# GPIO_Direct.net
KiCad netlist of a schematic drawn in Altium Designer
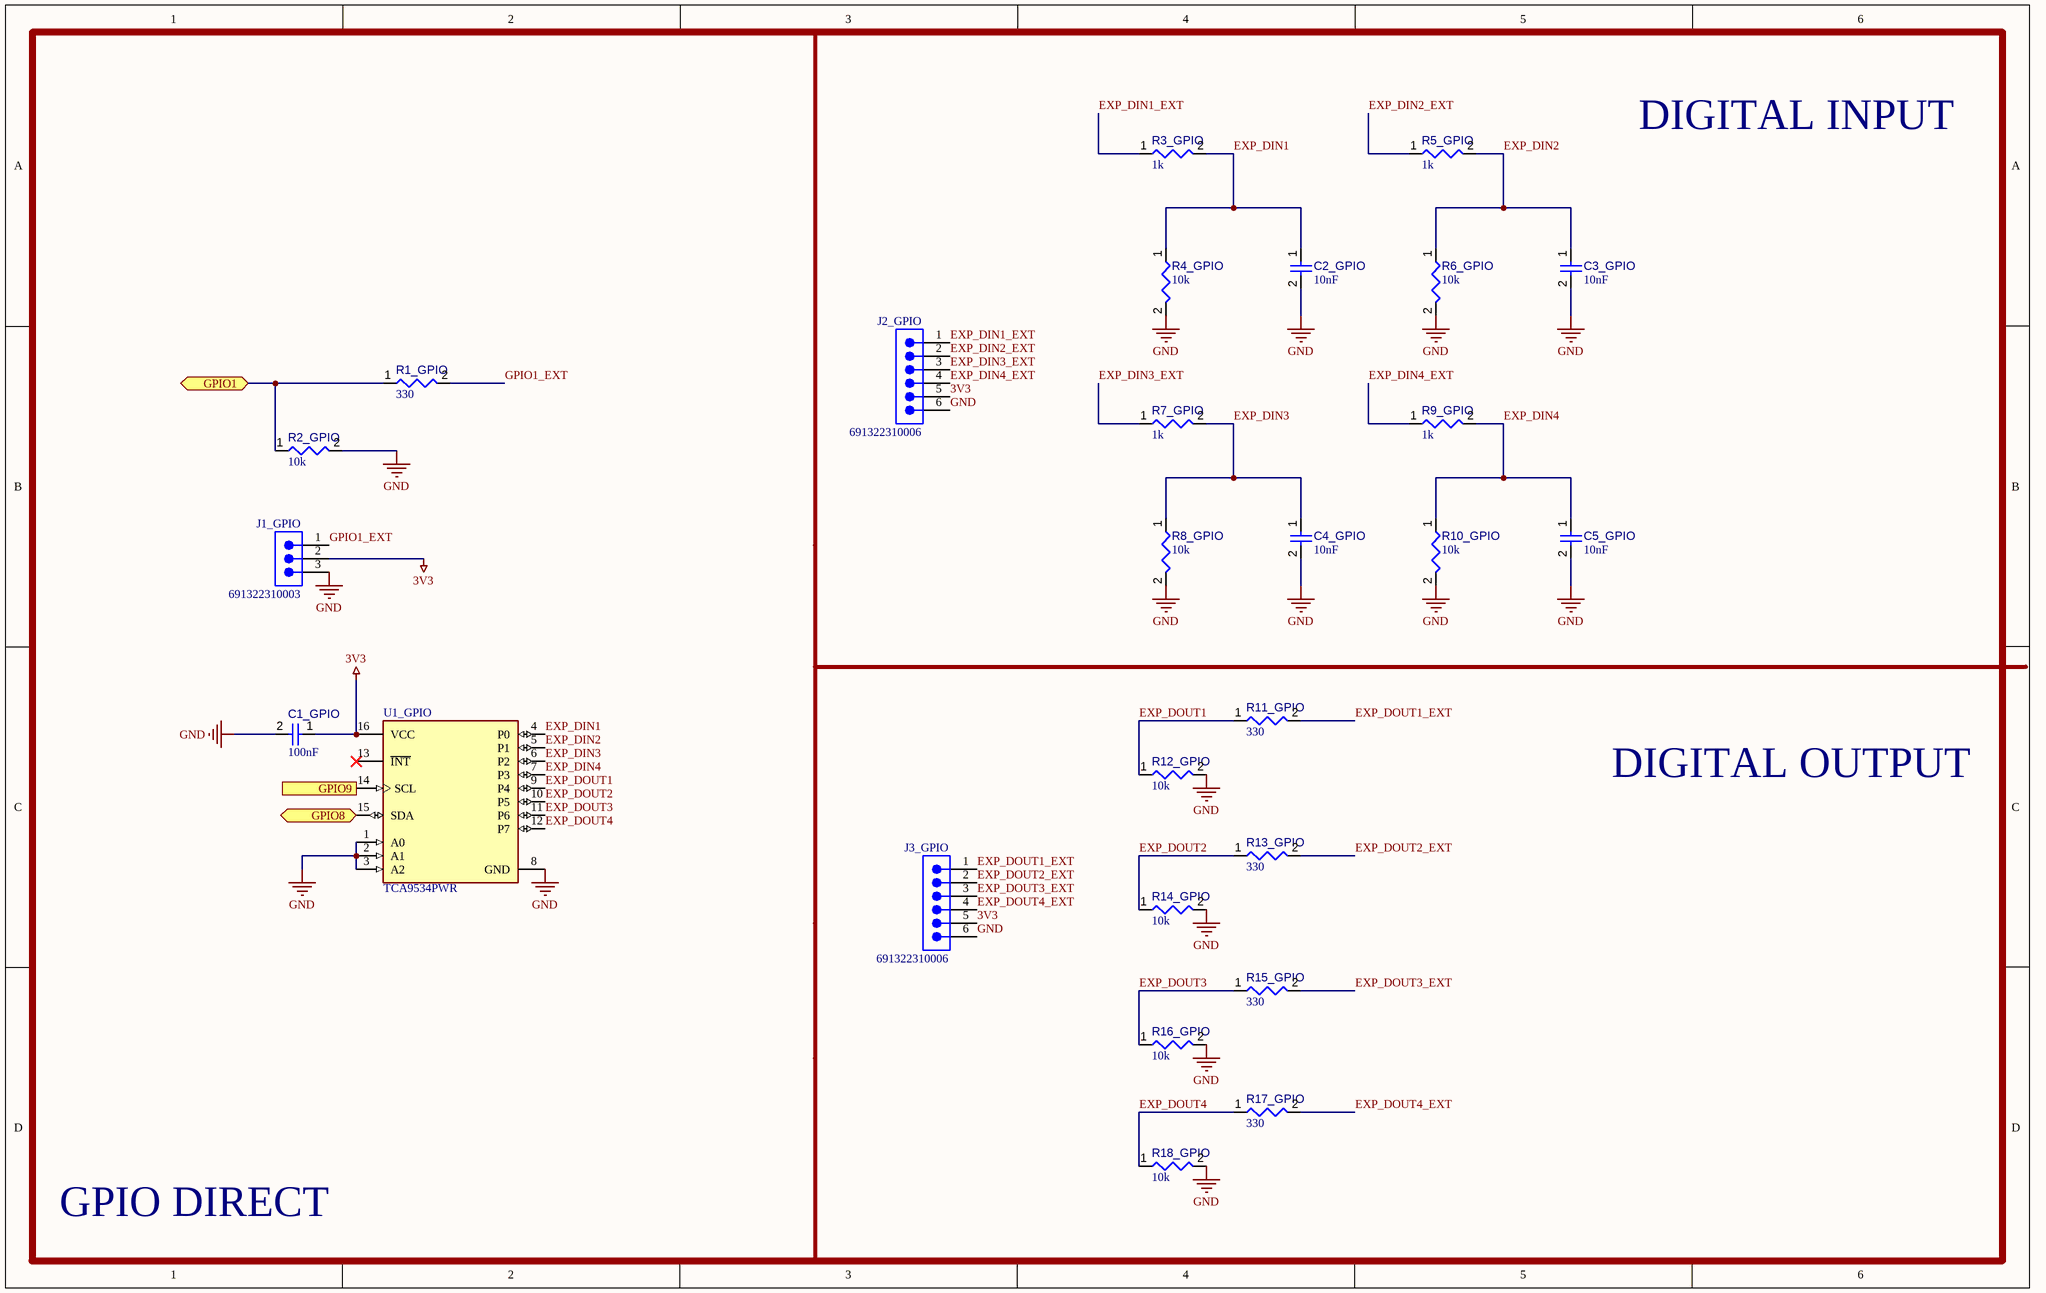
[diagram p0: GPIO Direct.SchDoc]

(export (version "E")
  (design (tool "Eeschema 10.0.6"))
  (components
    (comp (ref "C1_GPIO")
      (value "100nF")
      (footprint "CAPC1608X90X40NL10T20")
      (description "Chip Capacitor, 100 nF, +/- 10%, 50 V, 0603 (1608 Metric)")
      (fields (field (name "TOLERANCE") "10%") (field (name "Comment") "Capacitor 100 nF +/-10% 50 V 0603"))
      (libsource (lib "Faiz Agunda") (part "CAP-NP-2"))
    )
    (comp (ref "C2_GPIO")
      (value "10nF")
      (footprint "CAPC0402(1005)60_L")
      (description "Chip Capacitor, 10nF +/-20%, 50V, 0402, Thickness 0.6 mm")
      (fields (field (name "TOLERANCE") "5%") (field (name "Comment") "Capacitor 10nF +/-20% 50V 0402"))
      (libsource (lib "Faiz Agunda") (part "CAP-NP-2"))
    )
    (comp (ref "C3_GPIO")
      (value "10nF")
      (footprint "CAPC0402(1005)60_L")
      (description "Chip Capacitor, 10nF +/-20%, 50V, 0402, Thickness 0.6 mm")
      (fields (field (name "TOLERANCE") "5%") (field (name "Comment") "Capacitor 10nF +/-20% 50V 0402"))
      (libsource (lib "Faiz Agunda") (part "CAP-NP-2"))
    )
    (comp (ref "C4_GPIO")
      (value "10nF")
      (footprint "CAPC0402(1005)60_L")
      (description "Chip Capacitor, 10nF +/-20%, 50V, 0402, Thickness 0.6 mm")
      (fields (field (name "TOLERANCE") "5%") (field (name "Comment") "Capacitor 10nF +/-20% 50V 0402"))
      (libsource (lib "Faiz Agunda") (part "CAP-NP-2"))
    )
    (comp (ref "C5_GPIO")
      (value "10nF")
      (footprint "CAPC0402(1005)60_L")
      (description "Chip Capacitor, 10nF +/-20%, 50V, 0402, Thickness 0.6 mm")
      (fields (field (name "TOLERANCE") "5%") (field (name "Comment") "Capacitor 10nF +/-20% 50V 0402"))
      (libsource (lib "Faiz Agunda") (part "CAP-NP-2"))
    )
    (comp (ref "J1_GPIO")
      (value "691322310003")
      (footprint "691322310003")
      (description "Wurth Elektronik 3.81mmpitch3pPlug-in terminal blocks socket head, 322series, 300.0 v, welding")
      (fields (field (name "VOLTAGE") "300V"))
      (libsource (lib "Faiz Agunda") (part "TBL - 1R - 03P - Male"))
    )
    (comp (ref "J2_GPIO")
      (value "691322310006")
      (footprint "691322310006")
      (description "Wurth Elektronik 3.81mmpitch6pPlug-in terminal blocks socket head, 322series, 300.0 v, welding")
      (fields (field (name "VOLTAGE") "300V"))
      (libsource (lib "Faiz Agunda") (part "TBL - 1R - 06P - Male"))
    )
    (comp (ref "J3_GPIO")
      (value "691322310006")
      (footprint "691322310006")
      (description "Wurth Elektronik 3.81mmpitch6pPlug-in terminal blocks socket head, 322series, 300.0 v, welding")
      (fields (field (name "VOLTAGE") "300V"))
      (libsource (lib "Faiz Agunda") (part "TBL - 1R - 06P - Male"))
    )
    (comp (ref "R1_GPIO")
      (value "330")
      (footprint "RESC0402(1005)_L")
      (description "Chip Resistor, 330 Ohms, +/-5 %, 63 mW, -55 to 155 degC, 0402")
      (fields (field (name "POWER") "63mW") (field (name "TOLERANCE") "5%"))
      (libsource (lib "Faiz Agunda") (part "RES-2"))
    )
    (comp (ref "R2_GPIO")
      (value "10k")
      (footprint "RESC0402(1005)_L")
      (description "Chip Resistor, 10 kOhms, +/-1 %, 63 mW, -55 to 125 degC, 0402")
      (fields (field (name "POWER") "63mW") (field (name "TOLERANCE") "1%"))
      (libsource (lib "Faiz Agunda") (part "RES-2"))
    )
    (comp (ref "R3_GPIO")
      (value "1k")
      (footprint "RESC1608X55X25ML10T15")
      (description "Chip Resistor, 1 KOhm, +/-1%, 0.1 W, -55 to 155 degC, 0603 (1608 Metric)")
      (fields (field (name "POWER") "100mW") (field (name "TOLERANCE") "1%"))
      (libsource (lib "Faiz Agunda") (part "RES-2"))
    )
    (comp (ref "R4_GPIO")
      (value "10k")
      (footprint "RESC1005X40X25ML05T05")
      (description "Chip Resistor, 10 KOhm, +/- 1%, 63 mW, -55 to 155 degC, 0402 (1005 Metric)")
      (fields (field (name "POWER") "63mW") (field (name "TOLERANCE") "1%"))
      (libsource (lib "Faiz Agunda") (part "RES-2"))
    )
    (comp (ref "R5_GPIO")
      (value "1k")
      (footprint "RESC1608X55X25ML10T15")
      (description "Chip Resistor, 1 KOhm, +/-1%, 0.1 W, -55 to 155 degC, 0603 (1608 Metric)")
      (fields (field (name "POWER") "100mW") (field (name "TOLERANCE") "1%"))
      (libsource (lib "Faiz Agunda") (part "RES-2"))
    )
    (comp (ref "R6_GPIO")
      (value "10k")
      (footprint "RESC1005X40X25ML05T05")
      (description "Chip Resistor, 10 KOhm, +/- 1%, 63 mW, -55 to 155 degC, 0402 (1005 Metric)")
      (fields (field (name "POWER") "63mW") (field (name "TOLERANCE") "1%"))
      (libsource (lib "Faiz Agunda") (part "RES-2"))
    )
    (comp (ref "R7_GPIO")
      (value "1k")
      (footprint "RESC1608X55X25ML10T15")
      (description "Chip Resistor, 1 KOhm, +/-1%, 0.1 W, -55 to 155 degC, 0603 (1608 Metric)")
      (fields (field (name "POWER") "100mW") (field (name "TOLERANCE") "1%"))
      (libsource (lib "Faiz Agunda") (part "RES-2"))
    )
    (comp (ref "R8_GPIO")
      (value "10k")
      (footprint "RESC1005X40X25ML05T05")
      (description "Chip Resistor, 10 KOhm, +/- 1%, 63 mW, -55 to 155 degC, 0402 (1005 Metric)")
      (fields (field (name "POWER") "63mW") (field (name "TOLERANCE") "1%"))
      (libsource (lib "Faiz Agunda") (part "RES-2"))
    )
    (comp (ref "R9_GPIO")
      (value "1k")
      (footprint "RESC1608X55X25ML10T15")
      (description "Chip Resistor, 1 KOhm, +/-1%, 0.1 W, -55 to 155 degC, 0603 (1608 Metric)")
      (fields (field (name "POWER") "100mW") (field (name "TOLERANCE") "1%"))
      (libsource (lib "Faiz Agunda") (part "RES-2"))
    )
    (comp (ref "R10_GPIO")
      (value "10k")
      (footprint "RESC1005X40X25ML05T05")
      (description "Chip Resistor, 10 KOhm, +/- 1%, 63 mW, -55 to 155 degC, 0402 (1005 Metric)")
      (fields (field (name "POWER") "63mW") (field (name "TOLERANCE") "1%"))
      (libsource (lib "Faiz Agunda") (part "RES-2"))
    )
    (comp (ref "R11_GPIO")
      (value "330")
      (footprint "RESC0402(1005)_L")
      (description "Chip Resistor, 330 Ohms, +/-5 %, 63 mW, -55 to 155 degC, 0402")
      (fields (field (name "POWER") "63mW") (field (name "TOLERANCE") "5%"))
      (libsource (lib "Faiz Agunda") (part "RES-2"))
    )
    (comp (ref "R12_GPIO")
      (value "10k")
      (footprint "RESC0402(1005)_L")
      (description "Chip Resistor, 10 kOhms, +/-1 %, 63 mW, -55 to 125 degC, 0402")
      (fields (field (name "POWER") "63mW") (field (name "TOLERANCE") "1%"))
      (libsource (lib "Faiz Agunda") (part "RES-2"))
    )
    (comp (ref "R13_GPIO")
      (value "330")
      (footprint "RESC0402(1005)_L")
      (description "Chip Resistor, 330 Ohms, +/-5 %, 63 mW, -55 to 155 degC, 0402")
      (fields (field (name "POWER") "63mW") (field (name "TOLERANCE") "5%"))
      (libsource (lib "Faiz Agunda") (part "RES-2"))
    )
    (comp (ref "R14_GPIO")
      (value "10k")
      (footprint "RESC0402(1005)_L")
      (description "Chip Resistor, 10 kOhms, +/-1 %, 63 mW, -55 to 125 degC, 0402")
      (fields (field (name "POWER") "63mW") (field (name "TOLERANCE") "1%"))
      (libsource (lib "Faiz Agunda") (part "RES-2"))
    )
    (comp (ref "R15_GPIO")
      (value "330")
      (footprint "RESC0402(1005)_L")
      (description "Chip Resistor, 330 Ohms, +/-5 %, 63 mW, -55 to 155 degC, 0402")
      (fields (field (name "POWER") "63mW") (field (name "TOLERANCE") "5%"))
      (libsource (lib "Faiz Agunda") (part "RES-2"))
    )
    (comp (ref "R16_GPIO")
      (value "10k")
      (footprint "RESC0402(1005)_L")
      (description "Chip Resistor, 10 kOhms, +/-1 %, 63 mW, -55 to 125 degC, 0402")
      (fields (field (name "POWER") "63mW") (field (name "TOLERANCE") "1%"))
      (libsource (lib "Faiz Agunda") (part "RES-2"))
    )
    (comp (ref "R17_GPIO")
      (value "330")
      (footprint "RESC0402(1005)_L")
      (description "Chip Resistor, 330 Ohms, +/-5 %, 63 mW, -55 to 155 degC, 0402")
      (fields (field (name "POWER") "63mW") (field (name "TOLERANCE") "5%"))
      (libsource (lib "Faiz Agunda") (part "RES-2"))
    )
    (comp (ref "R18_GPIO")
      (value "10k")
      (footprint "RESC0402(1005)_L")
      (description "Chip Resistor, 10 kOhms, +/-1 %, 63 mW, -55 to 125 degC, 0402")
      (fields (field (name "POWER") "63mW") (field (name "TOLERANCE") "1%"))
      (libsource (lib "Faiz Agunda") (part "RES-2"))
    )
    (comp (ref "U1_GPIO")
      (value "TCA9534PWR")
      (footprint "FP-PW0016A-IPC_B")
      (description "10mA 25mA I2C 8 1.65V 5.5V 400KHz yes TSSOP-16 SMD mount，glue mount 1.2mm(height)")
      (libsource (lib "Faiz Agunda") (part "04628dd91dbb09866b58f3fb2ae999f"))
    )
  )
  (nets
    (net (code "1") (name "/EXP_DIN1") (class "Default")
      (node (ref "C2_GPIO") (pin "1") (pinfunction "1_1") (pintype "passive"))
      (node (ref "R3_GPIO") (pin "2") (pinfunction "2_2") (pintype "passive"))
      (node (ref "R4_GPIO") (pin "1") (pinfunction "1_1") (pintype "passive"))
      (node (ref "U1_GPIO") (pin "4") (pinfunction "P0_4") (pintype "bidirectional"))
    )
    (net (code "2") (name "/EXP_DIN1_EXT") (class "Default")
      (node (ref "J2_GPIO") (pin "1") (pinfunction "1_1") (pintype "passive"))
      (node (ref "R3_GPIO") (pin "1") (pinfunction "1_1") (pintype "passive"))
    )
    (net (code "3") (name "/EXP_DIN2") (class "Default")
      (node (ref "C3_GPIO") (pin "1") (pinfunction "1_1") (pintype "passive"))
      (node (ref "R5_GPIO") (pin "2") (pinfunction "2_2") (pintype "passive"))
      (node (ref "R6_GPIO") (pin "1") (pinfunction "1_1") (pintype "passive"))
      (node (ref "U1_GPIO") (pin "5") (pinfunction "P1_5") (pintype "bidirectional"))
    )
    (net (code "4") (name "/EXP_DIN2_EXT") (class "Default")
      (node (ref "J2_GPIO") (pin "2") (pinfunction "2_2") (pintype "passive"))
      (node (ref "R5_GPIO") (pin "1") (pinfunction "1_1") (pintype "passive"))
    )
    (net (code "5") (name "/EXP_DIN3") (class "Default")
      (node (ref "C4_GPIO") (pin "1") (pinfunction "1_1") (pintype "passive"))
      (node (ref "R7_GPIO") (pin "2") (pinfunction "2_2") (pintype "passive"))
      (node (ref "R8_GPIO") (pin "1") (pinfunction "1_1") (pintype "passive"))
      (node (ref "U1_GPIO") (pin "6") (pinfunction "P2_6") (pintype "bidirectional"))
    )
    (net (code "6") (name "/EXP_DIN3_EXT") (class "Default")
      (node (ref "J2_GPIO") (pin "3") (pinfunction "3_3") (pintype "passive"))
      (node (ref "R7_GPIO") (pin "1") (pinfunction "1_1") (pintype "passive"))
    )
    (net (code "7") (name "/EXP_DIN4") (class "Default")
      (node (ref "C5_GPIO") (pin "1") (pinfunction "1_1") (pintype "passive"))
      (node (ref "R10_GPIO") (pin "1") (pinfunction "1_1") (pintype "passive"))
      (node (ref "R9_GPIO") (pin "2") (pinfunction "2_2") (pintype "passive"))
      (node (ref "U1_GPIO") (pin "7") (pinfunction "P3_7") (pintype "bidirectional"))
    )
    (net (code "8") (name "/EXP_DIN4_EXT") (class "Default")
      (node (ref "J2_GPIO") (pin "4") (pinfunction "4_4") (pintype "passive"))
      (node (ref "R9_GPIO") (pin "1") (pinfunction "1_1") (pintype "passive"))
    )
    (net (code "9") (name "/EXP_DOUT1") (class "Default")
      (node (ref "R11_GPIO") (pin "1") (pinfunction "1_1") (pintype "passive"))
      (node (ref "R12_GPIO") (pin "1") (pinfunction "1_1") (pintype "passive"))
      (node (ref "U1_GPIO") (pin "9") (pinfunction "P4_9") (pintype "bidirectional"))
    )
    (net (code "10") (name "/EXP_DOUT1_EXT") (class "Default")
      (node (ref "J3_GPIO") (pin "1") (pinfunction "1_1") (pintype "passive"))
      (node (ref "R11_GPIO") (pin "2") (pinfunction "2_2") (pintype "passive"))
    )
    (net (code "11") (name "/EXP_DOUT2") (class "Default")
      (node (ref "R13_GPIO") (pin "1") (pinfunction "1_1") (pintype "passive"))
      (node (ref "R14_GPIO") (pin "1") (pinfunction "1_1") (pintype "passive"))
      (node (ref "U1_GPIO") (pin "10") (pinfunction "P5_10") (pintype "bidirectional"))
    )
    (net (code "12") (name "/EXP_DOUT2_EXT") (class "Default")
      (node (ref "J3_GPIO") (pin "2") (pinfunction "2_2") (pintype "passive"))
      (node (ref "R13_GPIO") (pin "2") (pinfunction "2_2") (pintype "passive"))
    )
    (net (code "13") (name "/EXP_DOUT3") (class "Default")
      (node (ref "R15_GPIO") (pin "1") (pinfunction "1_1") (pintype "passive"))
      (node (ref "R16_GPIO") (pin "1") (pinfunction "1_1") (pintype "passive"))
      (node (ref "U1_GPIO") (pin "11") (pinfunction "P6_11") (pintype "bidirectional"))
    )
    (net (code "14") (name "/EXP_DOUT3_EXT") (class "Default")
      (node (ref "J3_GPIO") (pin "3") (pinfunction "3_3") (pintype "passive"))
      (node (ref "R15_GPIO") (pin "2") (pinfunction "2_2") (pintype "passive"))
    )
    (net (code "15") (name "/EXP_DOUT4") (class "Default")
      (node (ref "R17_GPIO") (pin "1") (pinfunction "1_1") (pintype "passive"))
      (node (ref "R18_GPIO") (pin "1") (pinfunction "1_1") (pintype "passive"))
      (node (ref "U1_GPIO") (pin "12") (pinfunction "P7_12") (pintype "bidirectional"))
    )
    (net (code "16") (name "/EXP_DOUT4_EXT") (class "Default")
      (node (ref "J3_GPIO") (pin "4") (pinfunction "4_4") (pintype "passive"))
      (node (ref "R17_GPIO") (pin "2") (pinfunction "2_2") (pintype "passive"))
    )
    (net (code "17") (name "/GPIO1") (class "Default")
      (node (ref "R1_GPIO") (pin "1") (pinfunction "1_1") (pintype "passive"))
      (node (ref "R2_GPIO") (pin "1") (pinfunction "1_1") (pintype "passive"))
    )
    (net (code "18") (name "/GPIO1_EXT") (class "Default")
      (node (ref "J1_GPIO") (pin "1") (pinfunction "1_1") (pintype "passive"))
      (node (ref "R1_GPIO") (pin "2") (pinfunction "2_2") (pintype "passive"))
    )
    (net (code "19") (name "/GPIO8") (class "Default")
      (node (ref "U1_GPIO") (pin "15") (pinfunction "SDA_15") (pintype "bidirectional"))
    )
    (net (code "20") (name "/GPIO9") (class "Default")
      (node (ref "U1_GPIO") (pin "14") (pinfunction "SCL_14") (pintype "input"))
    )
    (net (code "21") (name "3V3") (class "Default")
      (node (ref "C1_GPIO") (pin "1") (pinfunction "1_1") (pintype "passive"))
      (node (ref "J1_GPIO") (pin "2") (pinfunction "2_2") (pintype "passive"))
      (node (ref "J2_GPIO") (pin "5") (pinfunction "5_5") (pintype "passive"))
      (node (ref "J3_GPIO") (pin "5") (pinfunction "5_5") (pintype "passive"))
      (node (ref "U1_GPIO") (pin "16") (pinfunction "VCC_16") (pintype "power_in"))
    )
    (net (code "22") (name "GND") (class "Default")
      (node (ref "C1_GPIO") (pin "2") (pinfunction "2_2") (pintype "passive"))
      (node (ref "C2_GPIO") (pin "2") (pinfunction "2_2") (pintype "passive"))
      (node (ref "C3_GPIO") (pin "2") (pinfunction "2_2") (pintype "passive"))
      (node (ref "C4_GPIO") (pin "2") (pinfunction "2_2") (pintype "passive"))
      (node (ref "C5_GPIO") (pin "2") (pinfunction "2_2") (pintype "passive"))
      (node (ref "J1_GPIO") (pin "3") (pinfunction "3_3") (pintype "passive"))
      (node (ref "J2_GPIO") (pin "6") (pinfunction "6_6") (pintype "passive"))
      (node (ref "J3_GPIO") (pin "6") (pinfunction "6_6") (pintype "passive"))
      (node (ref "R10_GPIO") (pin "2") (pinfunction "2_2") (pintype "passive"))
      (node (ref "R12_GPIO") (pin "2") (pinfunction "2_2") (pintype "passive"))
      (node (ref "R14_GPIO") (pin "2") (pinfunction "2_2") (pintype "passive"))
      (node (ref "R16_GPIO") (pin "2") (pinfunction "2_2") (pintype "passive"))
      (node (ref "R18_GPIO") (pin "2") (pinfunction "2_2") (pintype "passive"))
      (node (ref "R2_GPIO") (pin "2") (pinfunction "2_2") (pintype "passive"))
      (node (ref "R4_GPIO") (pin "2") (pinfunction "2_2") (pintype "passive"))
      (node (ref "R6_GPIO") (pin "2") (pinfunction "2_2") (pintype "passive"))
      (node (ref "R8_GPIO") (pin "2") (pinfunction "2_2") (pintype "passive"))
      (node (ref "U1_GPIO") (pin "1") (pinfunction "A0_1") (pintype "input"))
      (node (ref "U1_GPIO") (pin "2") (pinfunction "A1_2") (pintype "input"))
      (node (ref "U1_GPIO") (pin "3") (pinfunction "A2_3") (pintype "input"))
      (node (ref "U1_GPIO") (pin "8") (pinfunction "GND_8") (pintype "power_in"))
    )
    (net (code "23") (name "unconnected-(U1_GPIO-~{INT}-Pad13)") (class "Default")
      (node (ref "U1_GPIO") (pin "13") (pinfunction "~{INT}_13") (pintype "open_collector+no_connect"))
    )
  )
)
